# untitled_old.net
KiCad netlist of a schematic drawn in EAGLE
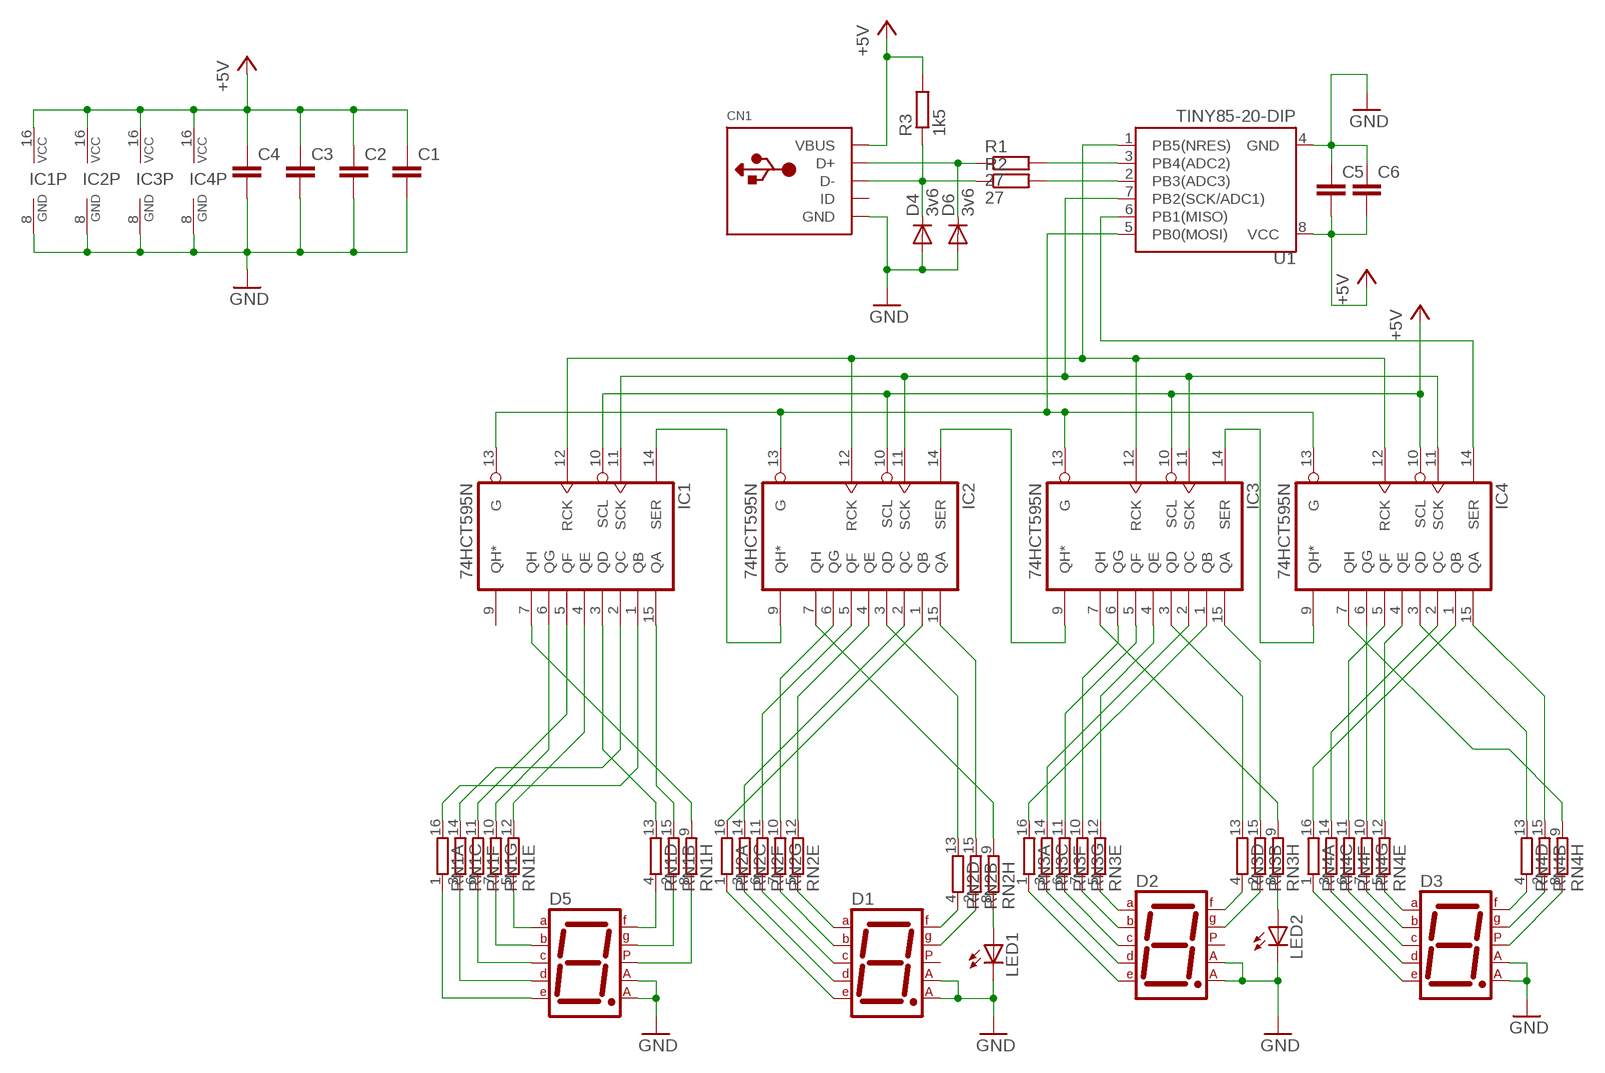
[diagram p0: schematic, sheet 1]

(export (version "E")
  (design (tool "Eeschema 10.0.6"))
  (components
    (comp (ref "C1")
      (value "C-EU025-025X050")
      (footprint "eagle-import:C025-025X050")
      (libsource (lib "eagle-import") (part "C-EU025-025X050"))
    )
    (comp (ref "C2")
      (value "C-EU025-025X050")
      (footprint "eagle-import:C025-025X050")
      (libsource (lib "eagle-import") (part "C-EU025-025X050"))
    )
    (comp (ref "C3")
      (value "C-EU025-025X050")
      (footprint "eagle-import:C025-025X050")
      (libsource (lib "eagle-import") (part "C-EU025-025X050"))
    )
    (comp (ref "C4")
      (value "C-EU025-025X050")
      (footprint "eagle-import:C025-025X050")
      (libsource (lib "eagle-import") (part "C-EU025-025X050"))
    )
    (comp (ref "C5")
      (value "C-EU025-025X050")
      (footprint "eagle-import:C025-025X050")
      (libsource (lib "eagle-import") (part "C-EU025-025X050"))
    )
    (comp (ref "C6")
      (value "C-EU025-025X050")
      (footprint "eagle-import:C025-025X050")
      (libsource (lib "eagle-import") (part "C-EU025-025X050"))
    )
    (comp (ref "CN1")
      (value "USBTHM")
      (footprint "eagle-import:USB-MINIB-THM")
      (libsource (lib "eagle-import") (part "USBTHM"))
    )
    (comp (ref "D1")
      (value "7SEG-CA")
      (footprint "eagle-import:7SEG-13")
      (libsource (lib "eagle-import") (part "7SEG-CA"))
    )
    (comp (ref "D2")
      (value "7SEG-CA")
      (footprint "eagle-import:7SEG-13")
      (libsource (lib "eagle-import") (part "7SEG-CA"))
    )
    (comp (ref "D3")
      (value "7SEG-CA")
      (footprint "eagle-import:7SEG-13")
      (libsource (lib "eagle-import") (part "7SEG-CA"))
    )
    (comp (ref "D4")
      (value "3v6")
      (footprint "eagle-import:D-7.5")
      (libsource (lib "eagle-import") (part "DIODE-D-7.5"))
    )
    (comp (ref "D5")
      (value "7SEG-CA")
      (footprint "eagle-import:7SEG-13")
      (libsource (lib "eagle-import") (part "7SEG-CA"))
    )
    (comp (ref "D6")
      (value "3v6")
      (footprint "eagle-import:D-7.5")
      (libsource (lib "eagle-import") (part "DIODE-D-7.5"))
    )
    (comp (ref "IC1")
      (value "74HCT595N")
      (footprint "eagle-import:DIL16")
      (libsource (lib "eagle-import") (part "74595NHCT"))
    )
    (comp (ref "IC2")
      (value "74HCT595N")
      (footprint "eagle-import:DIL16")
      (libsource (lib "eagle-import") (part "74595NHCT"))
    )
    (comp (ref "IC3")
      (value "74HCT595N")
      (footprint "eagle-import:DIL16")
      (libsource (lib "eagle-import") (part "74595NHCT"))
    )
    (comp (ref "IC4")
      (value "74HCT595N")
      (footprint "eagle-import:DIL16")
      (libsource (lib "eagle-import") (part "74595NHCT"))
    )
    (comp (ref "LED1")
      (value "LED3MM")
      (footprint "eagle-import:LED3MM")
      (libsource (lib "eagle-import") (part "LED3MM"))
    )
    (comp (ref "LED2")
      (value "LED3MM")
      (footprint "eagle-import:LED3MM")
      (libsource (lib "eagle-import") (part "LED3MM"))
    )
    (comp (ref "R1")
      (value "27")
      (footprint "eagle-import:0204_7")
      (libsource (lib "eagle-import") (part "R-EU_0204/7"))
    )
    (comp (ref "R2")
      (value "27")
      (footprint "eagle-import:0204_7")
      (libsource (lib "eagle-import") (part "R-EU_0204/7"))
    )
    (comp (ref "R3")
      (value "1k5")
      (footprint "eagle-import:0204_7")
      (libsource (lib "eagle-import") (part "R-EU_0204/7"))
    )
    (comp (ref "RN1")
      (value "8R-N")
      (footprint "eagle-import:DIL16")
      (libsource (lib "eagle-import") (part "8R-N"))
    )
    (comp (ref "RN2")
      (value "8R-N")
      (footprint "eagle-import:DIL16")
      (libsource (lib "eagle-import") (part "8R-N"))
    )
    (comp (ref "RN3")
      (value "8R-N")
      (footprint "eagle-import:DIL16")
      (libsource (lib "eagle-import") (part "8R-N"))
    )
    (comp (ref "RN4")
      (value "8R-N")
      (footprint "eagle-import:DIL16")
      (libsource (lib "eagle-import") (part "8R-N"))
    )
    (comp (ref "U1")
      (value "TINY85-20-DIP")
      (footprint "eagle-import:DIP08")
      (libsource (lib "eagle-import") (part "ATTINY45TINY85-20-DIP"))
    )
  )
  (nets
    (net (code "1") (name "+5V") (class "Default")
      (node (ref "C1") (pin "1") (pinfunction "1_1") (pintype "passive"))
      (node (ref "C2") (pin "1") (pinfunction "1_1") (pintype "passive"))
      (node (ref "C3") (pin "1") (pinfunction "1_1") (pintype "passive"))
      (node (ref "C4") (pin "1") (pinfunction "1_1") (pintype "passive"))
      (node (ref "C5") (pin "2") (pinfunction "2_2") (pintype "passive"))
      (node (ref "C6") (pin "2") (pinfunction "2_2") (pintype "passive"))
      (node (ref "CN1") (pin "VBUS") (pinfunction "VBUS_VBUS") (pintype "power_in"))
      (node (ref "IC1") (pin "10") (pinfunction "SCL_10") (pintype "input"))
      (node (ref "IC1") (pin "16") (pinfunction "VCC_16") (pintype "power_in"))
      (node (ref "IC2") (pin "10") (pinfunction "SCL_10") (pintype "input"))
      (node (ref "IC2") (pin "16") (pinfunction "VCC_16") (pintype "power_in"))
      (node (ref "IC3") (pin "10") (pinfunction "SCL_10") (pintype "input"))
      (node (ref "IC3") (pin "16") (pinfunction "VCC_16") (pintype "power_in"))
      (node (ref "IC4") (pin "10") (pinfunction "SCL_10") (pintype "input"))
      (node (ref "IC4") (pin "16") (pinfunction "VCC_16") (pintype "power_in"))
      (node (ref "R3") (pin "2") (pinfunction "2_2") (pintype "passive"))
      (node (ref "U1") (pin "8") (pinfunction "VCC_8") (pintype "bidirectional"))
    )
    (net (code "2") (name "GND") (class "Default")
      (node (ref "C1") (pin "2") (pinfunction "2_2") (pintype "passive"))
      (node (ref "C2") (pin "2") (pinfunction "2_2") (pintype "passive"))
      (node (ref "C3") (pin "2") (pinfunction "2_2") (pintype "passive"))
      (node (ref "C4") (pin "2") (pinfunction "2_2") (pintype "passive"))
      (node (ref "C5") (pin "1") (pinfunction "1_1") (pintype "passive"))
      (node (ref "C6") (pin "1") (pinfunction "1_1") (pintype "passive"))
      (node (ref "CN1") (pin "GND") (pinfunction "GND_GND") (pintype "power_in"))
      (node (ref "D1") (pin "3") (pinfunction "CA1_3") (pintype "passive"))
      (node (ref "D1") (pin "8") (pinfunction "CA2_8") (pintype "passive"))
      (node (ref "D2") (pin "3") (pinfunction "CA1_3") (pintype "passive"))
      (node (ref "D2") (pin "8") (pinfunction "CA2_8") (pintype "passive"))
      (node (ref "D3") (pin "3") (pinfunction "CA1_3") (pintype "passive"))
      (node (ref "D3") (pin "8") (pinfunction "CA2_8") (pintype "passive"))
      (node (ref "D4") (pin "A") (pinfunction "A_A") (pintype "passive"))
      (node (ref "D5") (pin "3") (pinfunction "CA1_3") (pintype "passive"))
      (node (ref "D5") (pin "8") (pinfunction "CA2_8") (pintype "passive"))
      (node (ref "D6") (pin "A") (pinfunction "A_A") (pintype "passive"))
      (node (ref "IC1") (pin "8") (pinfunction "GND_8") (pintype "power_in"))
      (node (ref "IC2") (pin "8") (pinfunction "GND_8") (pintype "power_in"))
      (node (ref "IC3") (pin "8") (pinfunction "GND_8") (pintype "power_in"))
      (node (ref "IC4") (pin "8") (pinfunction "GND_8") (pintype "power_in"))
      (node (ref "LED1") (pin "K") (pinfunction "C_K") (pintype "passive"))
      (node (ref "LED2") (pin "K") (pinfunction "C_K") (pintype "passive"))
      (node (ref "U1") (pin "4") (pinfunction "GND_4") (pintype "bidirectional"))
    )
    (net (code "3") (name "Net-(CN1-PadD+)") (class "Default")
      (node (ref "CN1") (pin "D+") (pinfunction "D+_D+") (pintype "bidirectional"))
      (node (ref "D6") (pin "C") (pinfunction "C_C") (pintype "passive"))
      (node (ref "R1") (pin "1") (pinfunction "1_1") (pintype "passive"))
    )
    (net (code "4") (name "Net-(CN1-PadD-)") (class "Default")
      (node (ref "CN1") (pin "D-") (pinfunction "D-_D-") (pintype "bidirectional"))
      (node (ref "D4") (pin "C") (pinfunction "C_C") (pintype "passive"))
      (node (ref "R2") (pin "1") (pinfunction "1_1") (pintype "passive"))
      (node (ref "R3") (pin "1") (pinfunction "1_1") (pintype "passive"))
    )
    (net (code "5") (name "Net-(D1-A)") (class "Default")
      (node (ref "D1") (pin "7") (pinfunction "A_7") (pintype "passive"))
      (node (ref "RN2") (pin "5") (pinfunction "1_5") (pintype "passive"))
    )
    (net (code "6") (name "Net-(D1-B)") (class "Default")
      (node (ref "D1") (pin "6") (pinfunction "B_6") (pintype "passive"))
      (node (ref "RN2") (pin "7") (pinfunction "1_7") (pintype "passive"))
    )
    (net (code "7") (name "Net-(D1-C)") (class "Default")
      (node (ref "D1") (pin "4") (pinfunction "C_4") (pintype "passive"))
      (node (ref "RN2") (pin "6") (pinfunction "1_6") (pintype "passive"))
    )
    (net (code "8") (name "Net-(D1-D)") (class "Default")
      (node (ref "D1") (pin "2") (pinfunction "D_2") (pintype "passive"))
      (node (ref "RN2") (pin "3") (pinfunction "1_3") (pintype "passive"))
    )
    (net (code "9") (name "Net-(D1-E)") (class "Default")
      (node (ref "D1") (pin "1") (pinfunction "E_1") (pintype "passive"))
      (node (ref "RN2") (pin "1") (pinfunction "1_1") (pintype "passive"))
    )
    (net (code "10") (name "Net-(D1-F)") (class "Default")
      (node (ref "D1") (pin "9") (pinfunction "F_9") (pintype "passive"))
      (node (ref "RN2") (pin "4") (pinfunction "1_4") (pintype "passive"))
    )
    (net (code "11") (name "Net-(D1-G)") (class "Default")
      (node (ref "D1") (pin "10") (pinfunction "G_10") (pintype "passive"))
      (node (ref "RN2") (pin "2") (pinfunction "1_2") (pintype "passive"))
    )
    (net (code "12") (name "Net-(D2-A)") (class "Default")
      (node (ref "D2") (pin "7") (pinfunction "A_7") (pintype "passive"))
      (node (ref "RN3") (pin "5") (pinfunction "1_5") (pintype "passive"))
    )
    (net (code "13") (name "Net-(D2-B)") (class "Default")
      (node (ref "D2") (pin "6") (pinfunction "B_6") (pintype "passive"))
      (node (ref "RN3") (pin "7") (pinfunction "1_7") (pintype "passive"))
    )
    (net (code "14") (name "Net-(D2-C)") (class "Default")
      (node (ref "D2") (pin "4") (pinfunction "C_4") (pintype "passive"))
      (node (ref "RN3") (pin "6") (pinfunction "1_6") (pintype "passive"))
    )
    (net (code "15") (name "Net-(D2-D)") (class "Default")
      (node (ref "D2") (pin "2") (pinfunction "D_2") (pintype "passive"))
      (node (ref "RN3") (pin "3") (pinfunction "1_3") (pintype "passive"))
    )
    (net (code "16") (name "Net-(D2-E)") (class "Default")
      (node (ref "D2") (pin "1") (pinfunction "E_1") (pintype "passive"))
      (node (ref "RN3") (pin "1") (pinfunction "1_1") (pintype "passive"))
    )
    (net (code "17") (name "Net-(D2-F)") (class "Default")
      (node (ref "D2") (pin "9") (pinfunction "F_9") (pintype "passive"))
      (node (ref "RN3") (pin "4") (pinfunction "1_4") (pintype "passive"))
    )
    (net (code "18") (name "Net-(D2-G)") (class "Default")
      (node (ref "D2") (pin "10") (pinfunction "G_10") (pintype "passive"))
      (node (ref "RN3") (pin "2") (pinfunction "1_2") (pintype "passive"))
    )
    (net (code "19") (name "Net-(D3-A)") (class "Default")
      (node (ref "D3") (pin "7") (pinfunction "A_7") (pintype "passive"))
      (node (ref "RN4") (pin "5") (pinfunction "1_5") (pintype "passive"))
    )
    (net (code "20") (name "Net-(D3-B)") (class "Default")
      (node (ref "D3") (pin "6") (pinfunction "B_6") (pintype "passive"))
      (node (ref "RN4") (pin "7") (pinfunction "1_7") (pintype "passive"))
    )
    (net (code "21") (name "Net-(D3-C)") (class "Default")
      (node (ref "D3") (pin "4") (pinfunction "C_4") (pintype "passive"))
      (node (ref "RN4") (pin "6") (pinfunction "1_6") (pintype "passive"))
    )
    (net (code "22") (name "Net-(D3-D)") (class "Default")
      (node (ref "D3") (pin "2") (pinfunction "D_2") (pintype "passive"))
      (node (ref "RN4") (pin "3") (pinfunction "1_3") (pintype "passive"))
    )
    (net (code "23") (name "Net-(D3-DP)") (class "Default")
      (node (ref "D3") (pin "5") (pinfunction "DP_5") (pintype "passive"))
      (node (ref "RN4") (pin "8") (pinfunction "1_8") (pintype "passive"))
    )
    (net (code "24") (name "Net-(D3-E)") (class "Default")
      (node (ref "D3") (pin "1") (pinfunction "E_1") (pintype "passive"))
      (node (ref "RN4") (pin "1") (pinfunction "1_1") (pintype "passive"))
    )
    (net (code "25") (name "Net-(D3-F)") (class "Default")
      (node (ref "D3") (pin "9") (pinfunction "F_9") (pintype "passive"))
      (node (ref "RN4") (pin "4") (pinfunction "1_4") (pintype "passive"))
    )
    (net (code "26") (name "Net-(D3-G)") (class "Default")
      (node (ref "D3") (pin "10") (pinfunction "G_10") (pintype "passive"))
      (node (ref "RN4") (pin "2") (pinfunction "1_2") (pintype "passive"))
    )
    (net (code "27") (name "Net-(D5-A)") (class "Default")
      (node (ref "D5") (pin "7") (pinfunction "A_7") (pintype "passive"))
      (node (ref "RN1") (pin "5") (pinfunction "1_5") (pintype "passive"))
    )
    (net (code "28") (name "Net-(D5-B)") (class "Default")
      (node (ref "D5") (pin "6") (pinfunction "B_6") (pintype "passive"))
      (node (ref "RN1") (pin "7") (pinfunction "1_7") (pintype "passive"))
    )
    (net (code "29") (name "Net-(D5-C)") (class "Default")
      (node (ref "D5") (pin "4") (pinfunction "C_4") (pintype "passive"))
      (node (ref "RN1") (pin "6") (pinfunction "1_6") (pintype "passive"))
    )
    (net (code "30") (name "Net-(D5-D)") (class "Default")
      (node (ref "D5") (pin "2") (pinfunction "D_2") (pintype "passive"))
      (node (ref "RN1") (pin "3") (pinfunction "1_3") (pintype "passive"))
    )
    (net (code "31") (name "Net-(D5-DP)") (class "Default")
      (node (ref "D5") (pin "5") (pinfunction "DP_5") (pintype "passive"))
      (node (ref "RN1") (pin "8") (pinfunction "1_8") (pintype "passive"))
    )
    (net (code "32") (name "Net-(D5-E)") (class "Default")
      (node (ref "D5") (pin "1") (pinfunction "E_1") (pintype "passive"))
      (node (ref "RN1") (pin "1") (pinfunction "1_1") (pintype "passive"))
    )
    (net (code "33") (name "Net-(D5-F)") (class "Default")
      (node (ref "D5") (pin "9") (pinfunction "F_9") (pintype "passive"))
      (node (ref "RN1") (pin "4") (pinfunction "1_4") (pintype "passive"))
    )
    (net (code "34") (name "Net-(D5-G)") (class "Default")
      (node (ref "D5") (pin "10") (pinfunction "G_10") (pintype "passive"))
      (node (ref "RN1") (pin "2") (pinfunction "1_2") (pintype "passive"))
    )
    (net (code "35") (name "Net-(IC1A-G)") (class "Default")
      (node (ref "IC1") (pin "13") (pinfunction "G_13") (pintype "input"))
      (node (ref "IC2") (pin "13") (pinfunction "G_13") (pintype "input"))
      (node (ref "IC3") (pin "13") (pinfunction "G_13") (pintype "input"))
      (node (ref "IC4") (pin "13") (pinfunction "G_13") (pintype "input"))
      (node (ref "U1") (pin "5") (pinfunction "PB0(MOSI)_5") (pintype "bidirectional"))
    )
    (net (code "36") (name "Net-(IC1A-QA)") (class "Default")
      (node (ref "IC1") (pin "15") (pinfunction "QA_15") (pintype "tri_state"))
      (node (ref "RN1") (pin "15") (pinfunction "2_15") (pintype "passive"))
    )
    (net (code "37") (name "Net-(IC1A-QB)") (class "Default")
      (node (ref "IC1") (pin "1") (pinfunction "QB_1") (pintype "tri_state"))
      (node (ref "RN1") (pin "16") (pinfunction "2_16") (pintype "passive"))
    )
    (net (code "38") (name "Net-(IC1A-QC)") (class "Default")
      (node (ref "IC1") (pin "2") (pinfunction "QC_2") (pintype "tri_state"))
      (node (ref "RN1") (pin "14") (pinfunction "2_14") (pintype "passive"))
    )
    (net (code "39") (name "Net-(IC1A-QD)") (class "Default")
      (node (ref "IC1") (pin "3") (pinfunction "QD_3") (pintype "tri_state"))
      (node (ref "RN1") (pin "13") (pinfunction "2_13") (pintype "passive"))
    )
    (net (code "40") (name "Net-(IC1A-QE)") (class "Default")
      (node (ref "IC1") (pin "4") (pinfunction "QE_4") (pintype "tri_state"))
      (node (ref "RN1") (pin "12") (pinfunction "2_12") (pintype "passive"))
    )
    (net (code "41") (name "Net-(IC1A-QF)") (class "Default")
      (node (ref "IC1") (pin "5") (pinfunction "QF_5") (pintype "tri_state"))
      (node (ref "RN1") (pin "11") (pinfunction "2_11") (pintype "passive"))
    )
    (net (code "42") (name "Net-(IC1A-QG)") (class "Default")
      (node (ref "IC1") (pin "6") (pinfunction "QG_6") (pintype "tri_state"))
      (node (ref "RN1") (pin "10") (pinfunction "2_10") (pintype "passive"))
    )
    (net (code "43") (name "Net-(IC1A-QH)") (class "Default")
      (node (ref "IC1") (pin "7") (pinfunction "QH_7") (pintype "tri_state"))
      (node (ref "RN1") (pin "9") (pinfunction "2_9") (pintype "passive"))
    )
    (net (code "44") (name "Net-(IC1A-RCK)") (class "Default")
      (node (ref "IC1") (pin "12") (pinfunction "RCK_12") (pintype "input"))
      (node (ref "IC2") (pin "12") (pinfunction "RCK_12") (pintype "input"))
      (node (ref "IC3") (pin "12") (pinfunction "RCK_12") (pintype "input"))
      (node (ref "IC4") (pin "12") (pinfunction "RCK_12") (pintype "input"))
      (node (ref "U1") (pin "1") (pinfunction "PB5(NRES)_1") (pintype "bidirectional"))
    )
    (net (code "45") (name "Net-(IC1A-SCK)") (class "Default")
      (node (ref "IC1") (pin "11") (pinfunction "SCK_11") (pintype "input"))
      (node (ref "IC2") (pin "11") (pinfunction "SCK_11") (pintype "input"))
      (node (ref "IC3") (pin "11") (pinfunction "SCK_11") (pintype "input"))
      (node (ref "IC4") (pin "11") (pinfunction "SCK_11") (pintype "input"))
      (node (ref "U1") (pin "7") (pinfunction "PB2(SCK/ADC1)_7") (pintype "bidirectional"))
    )
    (net (code "46") (name "Net-(IC1A-SER)") (class "Default")
      (node (ref "IC1") (pin "14") (pinfunction "SER_14") (pintype "input"))
      (node (ref "IC2") (pin "9") (pinfunction "QH*_9") (pintype "tri_state"))
    )
    (net (code "47") (name "Net-(IC2A-QA)") (class "Default")
      (node (ref "IC2") (pin "15") (pinfunction "QA_15") (pintype "tri_state"))
      (node (ref "RN2") (pin "15") (pinfunction "2_15") (pintype "passive"))
    )
    (net (code "48") (name "Net-(IC2A-QB)") (class "Default")
      (node (ref "IC2") (pin "1") (pinfunction "QB_1") (pintype "tri_state"))
      (node (ref "RN2") (pin "16") (pinfunction "2_16") (pintype "passive"))
    )
    (net (code "49") (name "Net-(IC2A-QC)") (class "Default")
      (node (ref "IC2") (pin "2") (pinfunction "QC_2") (pintype "tri_state"))
      (node (ref "RN2") (pin "14") (pinfunction "2_14") (pintype "passive"))
    )
    (net (code "50") (name "Net-(IC2A-QD)") (class "Default")
      (node (ref "IC2") (pin "3") (pinfunction "QD_3") (pintype "tri_state"))
      (node (ref "RN2") (pin "13") (pinfunction "2_13") (pintype "passive"))
    )
    (net (code "51") (name "Net-(IC2A-QE)") (class "Default")
      (node (ref "IC2") (pin "4") (pinfunction "QE_4") (pintype "tri_state"))
      (node (ref "RN2") (pin "12") (pinfunction "2_12") (pintype "passive"))
    )
    (net (code "52") (name "Net-(IC2A-QF)") (class "Default")
      (node (ref "IC2") (pin "5") (pinfunction "QF_5") (pintype "tri_state"))
      (node (ref "RN2") (pin "11") (pinfunction "2_11") (pintype "passive"))
    )
    (net (code "53") (name "Net-(IC2A-QG)") (class "Default")
      (node (ref "IC2") (pin "6") (pinfunction "QG_6") (pintype "tri_state"))
      (node (ref "RN2") (pin "10") (pinfunction "2_10") (pintype "passive"))
    )
    (net (code "54") (name "Net-(IC2A-QH)") (class "Default")
      (node (ref "IC2") (pin "7") (pinfunction "QH_7") (pintype "tri_state"))
      (node (ref "RN2") (pin "9") (pinfunction "2_9") (pintype "passive"))
    )
    (net (code "55") (name "Net-(IC2A-SER)") (class "Default")
      (node (ref "IC2") (pin "14") (pinfunction "SER_14") (pintype "input"))
      (node (ref "IC3") (pin "9") (pinfunction "QH*_9") (pintype "tri_state"))
    )
    (net (code "56") (name "Net-(IC3A-QA)") (class "Default")
      (node (ref "IC3") (pin "15") (pinfunction "QA_15") (pintype "tri_state"))
      (node (ref "RN3") (pin "15") (pinfunction "2_15") (pintype "passive"))
    )
    (net (code "57") (name "Net-(IC3A-QB)") (class "Default")
      (node (ref "IC3") (pin "1") (pinfunction "QB_1") (pintype "tri_state"))
      (node (ref "RN3") (pin "16") (pinfunction "2_16") (pintype "passive"))
    )
    (net (code "58") (name "Net-(IC3A-QC)") (class "Default")
      (node (ref "IC3") (pin "2") (pinfunction "QC_2") (pintype "tri_state"))
      (node (ref "RN3") (pin "14") (pinfunction "2_14") (pintype "passive"))
    )
    (net (code "59") (name "Net-(IC3A-QD)") (class "Default")
      (node (ref "IC3") (pin "3") (pinfunction "QD_3") (pintype "tri_state"))
      (node (ref "RN3") (pin "13") (pinfunction "2_13") (pintype "passive"))
    )
    (net (code "60") (name "Net-(IC3A-QE)") (class "Default")
      (node (ref "IC3") (pin "4") (pinfunction "QE_4") (pintype "tri_state"))
      (node (ref "RN3") (pin "12") (pinfunction "2_12") (pintype "passive"))
    )
    (net (code "61") (name "Net-(IC3A-QF)") (class "Default")
      (node (ref "IC3") (pin "5") (pinfunction "QF_5") (pintype "tri_state"))
      (node (ref "RN3") (pin "11") (pinfunction "2_11") (pintype "passive"))
    )
    (net (code "62") (name "Net-(IC3A-QG)") (class "Default")
      (node (ref "IC3") (pin "6") (pinfunction "QG_6") (pintype "tri_state"))
      (node (ref "RN3") (pin "10") (pinfunction "2_10") (pintype "passive"))
    )
    (net (code "63") (name "Net-(IC3A-QH)") (class "Default")
      (node (ref "IC3") (pin "7") (pinfunction "QH_7") (pintype "tri_state"))
      (node (ref "RN3") (pin "9") (pinfunction "2_9") (pintype "passive"))
    )
    (net (code "64") (name "Net-(IC3A-SER)") (class "Default")
      (node (ref "IC3") (pin "14") (pinfunction "SER_14") (pintype "input"))
      (node (ref "IC4") (pin "9") (pinfunction "QH*_9") (pintype "tri_state"))
    )
    (net (code "65") (name "Net-(IC4A-QA)") (class "Default")
      (node (ref "IC4") (pin "15") (pinfunction "QA_15") (pintype "tri_state"))
      (node (ref "RN4") (pin "15") (pinfunction "2_15") (pintype "passive"))
    )
    (net (code "66") (name "Net-(IC4A-QB)") (class "Default")
      (node (ref "IC4") (pin "1") (pinfunction "QB_1") (pintype "tri_state"))
      (node (ref "RN4") (pin "16") (pinfunction "2_16") (pintype "passive"))
    )
    (net (code "67") (name "Net-(IC4A-QC)") (class "Default")
      (node (ref "IC4") (pin "2") (pinfunction "QC_2") (pintype "tri_state"))
      (node (ref "RN4") (pin "14") (pinfunction "2_14") (pintype "passive"))
    )
    (net (code "68") (name "Net-(IC4A-QD)") (class "Default")
      (node (ref "IC4") (pin "3") (pinfunction "QD_3") (pintype "tri_state"))
      (node (ref "RN4") (pin "13") (pinfunction "2_13") (pintype "passive"))
    )
    (net (code "69") (name "Net-(IC4A-QE)") (class "Default")
      (node (ref "IC4") (pin "4") (pinfunction "QE_4") (pintype "tri_state"))
      (node (ref "RN4") (pin "12") (pinfunction "2_12") (pintype "passive"))
    )
    (net (code "70") (name "Net-(IC4A-QF)") (class "Default")
      (node (ref "IC4") (pin "5") (pinfunction "QF_5") (pintype "tri_state"))
      (node (ref "RN4") (pin "11") (pinfunction "2_11") (pintype "passive"))
    )
    (net (code "71") (name "Net-(IC4A-QG)") (class "Default")
      (node (ref "IC4") (pin "6") (pinfunction "QG_6") (pintype "tri_state"))
      (node (ref "RN4") (pin "10") (pinfunction "2_10") (pintype "passive"))
    )
    (net (code "72") (name "Net-(IC4A-QH)") (class "Default")
      (node (ref "IC4") (pin "7") (pinfunction "QH_7") (pintype "tri_state"))
      (node (ref "RN4") (pin "9") (pinfunction "2_9") (pintype "passive"))
    )
    (net (code "73") (name "Net-(IC4A-SER)") (class "Default")
      (node (ref "IC4") (pin "14") (pinfunction "SER_14") (pintype "input"))
      (node (ref "U1") (pin "6") (pinfunction "PB1(MISO)_6") (pintype "bidirectional"))
    )
    (net (code "74") (name "Net-(RN2H-1)") (class "Default")
      (node (ref "LED1") (pin "A") (pinfunction "A_A") (pintype "passive"))
      (node (ref "RN2") (pin "8") (pinfunction "1_8") (pintype "passive"))
    )
    (net (code "75") (name "Net-(RN3H-1)") (class "Default")
      (node (ref "LED2") (pin "A") (pinfunction "A_A") (pintype "passive"))
      (node (ref "RN3") (pin "8") (pinfunction "1_8") (pintype "passive"))
    )
    (net (code "76") (name "Net-(U1-PB3(ADC3))") (class "Default")
      (node (ref "R2") (pin "2") (pinfunction "2_2") (pintype "passive"))
      (node (ref "U1") (pin "2") (pinfunction "PB3(ADC3)_2") (pintype "bidirectional"))
    )
    (net (code "77") (name "Net-(U1-PB4(ADC2))") (class "Default")
      (node (ref "R1") (pin "2") (pinfunction "2_2") (pintype "passive"))
      (node (ref "U1") (pin "3") (pinfunction "PB4(ADC2)_3") (pintype "bidirectional"))
    )
    (net (code "78") (name "unconnected-(CN1-PadID)") (class "Default")
      (node (ref "CN1") (pin "ID") (pinfunction "ID_ID") (pintype "bidirectional"))
    )
    (net (code "79") (name "unconnected-(D1-DP-Pad5)") (class "Default")
      (node (ref "D1") (pin "5") (pinfunction "DP_5") (pintype "passive"))
    )
    (net (code "80") (name "unconnected-(D2-DP-Pad5)") (class "Default")
      (node (ref "D2") (pin "5") (pinfunction "DP_5") (pintype "passive"))
    )
    (net (code "81") (name "unconnected-(IC1A-QH*-Pad9)") (class "Default")
      (node (ref "IC1") (pin "9") (pinfunction "QH*_9") (pintype "tri_state"))
    )
  )
)
